# sch_smarthome.net
KiCad netlist of a schematic drawn in Altium Designer
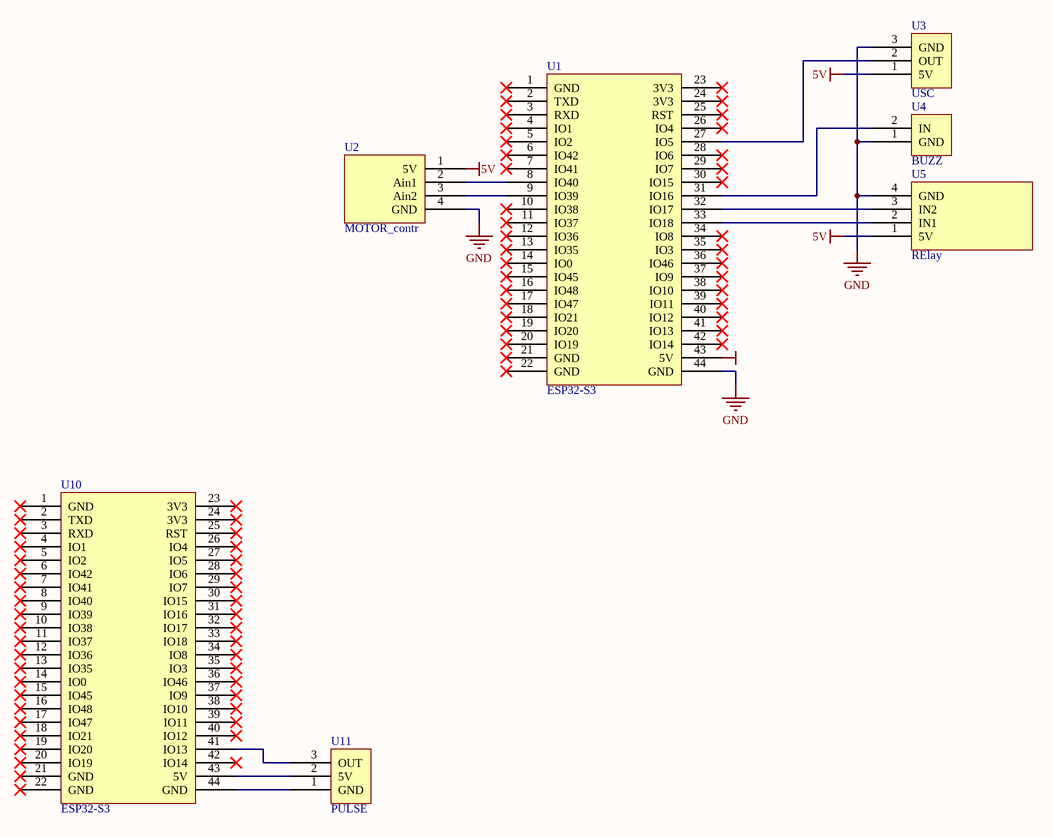
[diagram p0: sch_smarthome.SchDoc]

(export (version "E")
  (design (tool "Eeschema 10.0.6"))
  (components
    (comp (ref "U1") (value "ESP32-S3") (libsource (lib "First_PCB_dip") (part "ESP32-S3")))
    (comp (ref "U2") (value "MOTOR_contr") (libsource (lib "lib_htx") (part "MOTOR_contr")))
    (comp (ref "U3") (value "USC") (libsource (lib "lib_htx") (part "USC")))
    (comp (ref "U4") (value "BUZZ") (libsource (lib "lib_htx") (part "BUZZ")))
    (comp (ref "U5") (value "RElay") (libsource (lib "lib_htx") (part "RElay")))
    (comp (ref "U10") (value "ESP32-S3") (libsource (lib "First_PCB_dip") (part "ESP32-S3")))
    (comp (ref "U11") (value "PULSE") (libsource (lib "lib_htx") (part "PULSE")))
  )
  (nets
    (net (code "1") (name "5V") (class "Default")
      (node (ref "U2") (pin "1") (pinfunction "5V_1") (pintype "passive"))
      (node (ref "U3") (pin "1") (pinfunction "5V_1") (pintype "passive"))
      (node (ref "U5") (pin "1") (pinfunction "5V_1") (pintype "passive"))
    )
    (net (code "2") (name "<NO NET>") (class "Default")
      (node (ref "U1") (pin "43") (pinfunction "5V_43") (pintype "passive"))
    )
    (net (code "3") (name "GND") (class "Default")
      (node (ref "U1") (pin "44") (pinfunction "GND_44") (pintype "passive"))
      (node (ref "U2") (pin "4") (pinfunction "GND_4") (pintype "passive"))
      (node (ref "U3") (pin "3") (pinfunction "GND_3") (pintype "passive"))
      (node (ref "U4") (pin "1") (pinfunction "GND_1") (pintype "passive"))
      (node (ref "U5") (pin "4") (pinfunction "GND_4") (pintype "passive"))
    )
    (net (code "4") (name "Net-(U1-IO5)") (class "Default")
      (node (ref "U1") (pin "27") (pinfunction "IO5_27") (pintype "passive"))
      (node (ref "U3") (pin "2") (pinfunction "OUT_2") (pintype "passive"))
    )
    (net (code "5") (name "Net-(U1-IO16)") (class "Default")
      (node (ref "U1") (pin "31") (pinfunction "IO16_31") (pintype "passive"))
      (node (ref "U4") (pin "2") (pinfunction "IN_2") (pintype "passive"))
    )
    (net (code "6") (name "Net-(U1-IO17)") (class "Default")
      (node (ref "U1") (pin "32") (pinfunction "IO17_32") (pintype "passive"))
      (node (ref "U5") (pin "3") (pinfunction "IN2_3") (pintype "passive"))
    )
    (net (code "7") (name "Net-(U1-IO18)") (class "Default")
      (node (ref "U1") (pin "33") (pinfunction "IO18_33") (pintype "passive"))
      (node (ref "U5") (pin "2") (pinfunction "IN1_2") (pintype "passive"))
    )
    (net (code "8") (name "Net-(U1-IO39)") (class "Default")
      (node (ref "U1") (pin "9") (pinfunction "IO39_9") (pintype "passive"))
      (node (ref "U2") (pin "3") (pinfunction "Ain2_3") (pintype "passive"))
    )
    (net (code "9") (name "Net-(U1-IO40)") (class "Default")
      (node (ref "U1") (pin "8") (pinfunction "IO40_8") (pintype "passive"))
      (node (ref "U2") (pin "2") (pinfunction "Ain1_2") (pintype "passive"))
    )
    (net (code "10") (name "Net-(U10-5V)") (class "Default")
      (node (ref "U10") (pin "43") (pinfunction "5V_43") (pintype "passive"))
      (node (ref "U11") (pin "2") (pinfunction "5V_2") (pintype "passive"))
    )
    (net (code "11") (name "Net-(U10-IO13)") (class "Default")
      (node (ref "U10") (pin "41") (pinfunction "IO13_41") (pintype "passive"))
      (node (ref "U11") (pin "3") (pinfunction "OUT_3") (pintype "passive"))
    )
    (net (code "12") (name "Net-(U11-GND)") (class "Default")
      (node (ref "U10") (pin "44") (pinfunction "GND_44") (pintype "passive"))
      (node (ref "U11") (pin "1") (pinfunction "GND_1") (pintype "passive"))
    )
    (net (code "13") (name "unconnected-(U1-3V3-Pad23)") (class "Default")
      (node (ref "U1") (pin "23") (pinfunction "3V3_23") (pintype "passive+no_connect"))
    )
    (net (code "14") (name "unconnected-(U1-3V3-Pad24)") (class "Default")
      (node (ref "U1") (pin "24") (pinfunction "3V3_24") (pintype "passive+no_connect"))
    )
    (net (code "15") (name "unconnected-(U1-GND-Pad1)") (class "Default")
      (node (ref "U1") (pin "1") (pinfunction "GND_1") (pintype "passive+no_connect"))
    )
    (net (code "16") (name "unconnected-(U1-GND-Pad21)") (class "Default")
      (node (ref "U1") (pin "21") (pinfunction "GND_21") (pintype "passive+no_connect"))
    )
    (net (code "17") (name "unconnected-(U1-GND-Pad22)") (class "Default")
      (node (ref "U1") (pin "22") (pinfunction "GND_22") (pintype "passive+no_connect"))
    )
    (net (code "18") (name "unconnected-(U1-IO0-Pad14)") (class "Default")
      (node (ref "U1") (pin "14") (pinfunction "IO0_14") (pintype "passive+no_connect"))
    )
    (net (code "19") (name "unconnected-(U1-IO1-Pad4)") (class "Default")
      (node (ref "U1") (pin "4") (pinfunction "IO1_4") (pintype "passive+no_connect"))
    )
    (net (code "20") (name "unconnected-(U1-IO2-Pad5)") (class "Default")
      (node (ref "U1") (pin "5") (pinfunction "IO2_5") (pintype "passive+no_connect"))
    )
    (net (code "21") (name "unconnected-(U1-IO3-Pad35)") (class "Default")
      (node (ref "U1") (pin "35") (pinfunction "IO3_35") (pintype "passive+no_connect"))
    )
    (net (code "22") (name "unconnected-(U1-IO4-Pad26)") (class "Default")
      (node (ref "U1") (pin "26") (pinfunction "IO4_26") (pintype "passive+no_connect"))
    )
    (net (code "23") (name "unconnected-(U1-IO6-Pad28)") (class "Default")
      (node (ref "U1") (pin "28") (pinfunction "IO6_28") (pintype "passive+no_connect"))
    )
    (net (code "24") (name "unconnected-(U1-IO7-Pad29)") (class "Default")
      (node (ref "U1") (pin "29") (pinfunction "IO7_29") (pintype "passive+no_connect"))
    )
    (net (code "25") (name "unconnected-(U1-IO8-Pad34)") (class "Default")
      (node (ref "U1") (pin "34") (pinfunction "IO8_34") (pintype "passive+no_connect"))
    )
    (net (code "26") (name "unconnected-(U1-IO9-Pad37)") (class "Default")
      (node (ref "U1") (pin "37") (pinfunction "IO9_37") (pintype "passive+no_connect"))
    )
    (net (code "27") (name "unconnected-(U1-IO10-Pad38)") (class "Default")
      (node (ref "U1") (pin "38") (pinfunction "IO10_38") (pintype "passive+no_connect"))
    )
    (net (code "28") (name "unconnected-(U1-IO11-Pad39)") (class "Default")
      (node (ref "U1") (pin "39") (pinfunction "IO11_39") (pintype "passive+no_connect"))
    )
    (net (code "29") (name "unconnected-(U1-IO12-Pad40)") (class "Default")
      (node (ref "U1") (pin "40") (pinfunction "IO12_40") (pintype "passive+no_connect"))
    )
    (net (code "30") (name "unconnected-(U1-IO13-Pad41)") (class "Default")
      (node (ref "U1") (pin "41") (pinfunction "IO13_41") (pintype "passive+no_connect"))
    )
    (net (code "31") (name "unconnected-(U1-IO14-Pad42)") (class "Default")
      (node (ref "U1") (pin "42") (pinfunction "IO14_42") (pintype "passive+no_connect"))
    )
    (net (code "32") (name "unconnected-(U1-IO15-Pad30)") (class "Default")
      (node (ref "U1") (pin "30") (pinfunction "IO15_30") (pintype "passive+no_connect"))
    )
    (net (code "33") (name "unconnected-(U1-IO19-Pad20)") (class "Default")
      (node (ref "U1") (pin "20") (pinfunction "IO19_20") (pintype "passive+no_connect"))
    )
    (net (code "34") (name "unconnected-(U1-IO20-Pad19)") (class "Default")
      (node (ref "U1") (pin "19") (pinfunction "IO20_19") (pintype "passive+no_connect"))
    )
    (net (code "35") (name "unconnected-(U1-IO21-Pad18)") (class "Default")
      (node (ref "U1") (pin "18") (pinfunction "IO21_18") (pintype "passive+no_connect"))
    )
    (net (code "36") (name "unconnected-(U1-IO35-Pad13)") (class "Default")
      (node (ref "U1") (pin "13") (pinfunction "IO35_13") (pintype "passive+no_connect"))
    )
    (net (code "37") (name "unconnected-(U1-IO36-Pad12)") (class "Default")
      (node (ref "U1") (pin "12") (pinfunction "IO36_12") (pintype "passive+no_connect"))
    )
    (net (code "38") (name "unconnected-(U1-IO37-Pad11)") (class "Default")
      (node (ref "U1") (pin "11") (pinfunction "IO37_11") (pintype "passive+no_connect"))
    )
    (net (code "39") (name "unconnected-(U1-IO38-Pad10)") (class "Default")
      (node (ref "U1") (pin "10") (pinfunction "IO38_10") (pintype "passive+no_connect"))
    )
    (net (code "40") (name "unconnected-(U1-IO41-Pad7)") (class "Default")
      (node (ref "U1") (pin "7") (pinfunction "IO41_7") (pintype "passive+no_connect"))
    )
    (net (code "41") (name "unconnected-(U1-IO42-Pad6)") (class "Default")
      (node (ref "U1") (pin "6") (pinfunction "IO42_6") (pintype "passive+no_connect"))
    )
    (net (code "42") (name "unconnected-(U1-IO45-Pad15)") (class "Default")
      (node (ref "U1") (pin "15") (pinfunction "IO45_15") (pintype "passive+no_connect"))
    )
    (net (code "43") (name "unconnected-(U1-IO46-Pad36)") (class "Default")
      (node (ref "U1") (pin "36") (pinfunction "IO46_36") (pintype "passive+no_connect"))
    )
    (net (code "44") (name "unconnected-(U1-IO47-Pad17)") (class "Default")
      (node (ref "U1") (pin "17") (pinfunction "IO47_17") (pintype "passive+no_connect"))
    )
    (net (code "45") (name "unconnected-(U1-IO48-Pad16)") (class "Default")
      (node (ref "U1") (pin "16") (pinfunction "IO48_16") (pintype "passive+no_connect"))
    )
    (net (code "46") (name "unconnected-(U1-RST-Pad25)") (class "Default")
      (node (ref "U1") (pin "25") (pinfunction "RST_25") (pintype "passive+no_connect"))
    )
    (net (code "47") (name "unconnected-(U1-RXD-Pad3)") (class "Default")
      (node (ref "U1") (pin "3") (pinfunction "RXD_3") (pintype "passive+no_connect"))
    )
    (net (code "48") (name "unconnected-(U1-TXD-Pad2)") (class "Default")
      (node (ref "U1") (pin "2") (pinfunction "TXD_2") (pintype "passive+no_connect"))
    )
    (net (code "49") (name "unconnected-(U10-3V3-Pad23)") (class "Default")
      (node (ref "U10") (pin "23") (pinfunction "3V3_23") (pintype "passive+no_connect"))
    )
    (net (code "50") (name "unconnected-(U10-3V3-Pad24)") (class "Default")
      (node (ref "U10") (pin "24") (pinfunction "3V3_24") (pintype "passive+no_connect"))
    )
    (net (code "51") (name "unconnected-(U10-GND-Pad1)") (class "Default")
      (node (ref "U10") (pin "1") (pinfunction "GND_1") (pintype "passive+no_connect"))
    )
    (net (code "52") (name "unconnected-(U10-GND-Pad21)") (class "Default")
      (node (ref "U10") (pin "21") (pinfunction "GND_21") (pintype "passive+no_connect"))
    )
    (net (code "53") (name "unconnected-(U10-GND-Pad22)") (class "Default")
      (node (ref "U10") (pin "22") (pinfunction "GND_22") (pintype "passive+no_connect"))
    )
    (net (code "54") (name "unconnected-(U10-IO0-Pad14)") (class "Default")
      (node (ref "U10") (pin "14") (pinfunction "IO0_14") (pintype "passive+no_connect"))
    )
    (net (code "55") (name "unconnected-(U10-IO1-Pad4)") (class "Default")
      (node (ref "U10") (pin "4") (pinfunction "IO1_4") (pintype "passive+no_connect"))
    )
    (net (code "56") (name "unconnected-(U10-IO2-Pad5)") (class "Default")
      (node (ref "U10") (pin "5") (pinfunction "IO2_5") (pintype "passive+no_connect"))
    )
    (net (code "57") (name "unconnected-(U10-IO3-Pad35)") (class "Default")
      (node (ref "U10") (pin "35") (pinfunction "IO3_35") (pintype "passive+no_connect"))
    )
    (net (code "58") (name "unconnected-(U10-IO4-Pad26)") (class "Default")
      (node (ref "U10") (pin "26") (pinfunction "IO4_26") (pintype "passive+no_connect"))
    )
    (net (code "59") (name "unconnected-(U10-IO5-Pad27)") (class "Default")
      (node (ref "U10") (pin "27") (pinfunction "IO5_27") (pintype "passive+no_connect"))
    )
    (net (code "60") (name "unconnected-(U10-IO6-Pad28)") (class "Default")
      (node (ref "U10") (pin "28") (pinfunction "IO6_28") (pintype "passive+no_connect"))
    )
    (net (code "61") (name "unconnected-(U10-IO7-Pad29)") (class "Default")
      (node (ref "U10") (pin "29") (pinfunction "IO7_29") (pintype "passive+no_connect"))
    )
    (net (code "62") (name "unconnected-(U10-IO8-Pad34)") (class "Default")
      (node (ref "U10") (pin "34") (pinfunction "IO8_34") (pintype "passive+no_connect"))
    )
    (net (code "63") (name "unconnected-(U10-IO9-Pad37)") (class "Default")
      (node (ref "U10") (pin "37") (pinfunction "IO9_37") (pintype "passive+no_connect"))
    )
    (net (code "64") (name "unconnected-(U10-IO10-Pad38)") (class "Default")
      (node (ref "U10") (pin "38") (pinfunction "IO10_38") (pintype "passive+no_connect"))
    )
    (net (code "65") (name "unconnected-(U10-IO11-Pad39)") (class "Default")
      (node (ref "U10") (pin "39") (pinfunction "IO11_39") (pintype "passive+no_connect"))
    )
    (net (code "66") (name "unconnected-(U10-IO12-Pad40)") (class "Default")
      (node (ref "U10") (pin "40") (pinfunction "IO12_40") (pintype "passive+no_connect"))
    )
    (net (code "67") (name "unconnected-(U10-IO14-Pad42)") (class "Default")
      (node (ref "U10") (pin "42") (pinfunction "IO14_42") (pintype "passive+no_connect"))
    )
    (net (code "68") (name "unconnected-(U10-IO15-Pad30)") (class "Default")
      (node (ref "U10") (pin "30") (pinfunction "IO15_30") (pintype "passive+no_connect"))
    )
    (net (code "69") (name "unconnected-(U10-IO16-Pad31)") (class "Default")
      (node (ref "U10") (pin "31") (pinfunction "IO16_31") (pintype "passive+no_connect"))
    )
    (net (code "70") (name "unconnected-(U10-IO17-Pad32)") (class "Default")
      (node (ref "U10") (pin "32") (pinfunction "IO17_32") (pintype "passive+no_connect"))
    )
    (net (code "71") (name "unconnected-(U10-IO18-Pad33)") (class "Default")
      (node (ref "U10") (pin "33") (pinfunction "IO18_33") (pintype "passive+no_connect"))
    )
    (net (code "72") (name "unconnected-(U10-IO19-Pad20)") (class "Default")
      (node (ref "U10") (pin "20") (pinfunction "IO19_20") (pintype "passive+no_connect"))
    )
    (net (code "73") (name "unconnected-(U10-IO20-Pad19)") (class "Default")
      (node (ref "U10") (pin "19") (pinfunction "IO20_19") (pintype "passive+no_connect"))
    )
    (net (code "74") (name "unconnected-(U10-IO21-Pad18)") (class "Default")
      (node (ref "U10") (pin "18") (pinfunction "IO21_18") (pintype "passive+no_connect"))
    )
    (net (code "75") (name "unconnected-(U10-IO35-Pad13)") (class "Default")
      (node (ref "U10") (pin "13") (pinfunction "IO35_13") (pintype "passive+no_connect"))
    )
    (net (code "76") (name "unconnected-(U10-IO36-Pad12)") (class "Default")
      (node (ref "U10") (pin "12") (pinfunction "IO36_12") (pintype "passive+no_connect"))
    )
    (net (code "77") (name "unconnected-(U10-IO37-Pad11)") (class "Default")
      (node (ref "U10") (pin "11") (pinfunction "IO37_11") (pintype "passive+no_connect"))
    )
    (net (code "78") (name "unconnected-(U10-IO38-Pad10)") (class "Default")
      (node (ref "U10") (pin "10") (pinfunction "IO38_10") (pintype "passive+no_connect"))
    )
    (net (code "79") (name "unconnected-(U10-IO39-Pad9)") (class "Default")
      (node (ref "U10") (pin "9") (pinfunction "IO39_9") (pintype "passive+no_connect"))
    )
    (net (code "80") (name "unconnected-(U10-IO40-Pad8)") (class "Default")
      (node (ref "U10") (pin "8") (pinfunction "IO40_8") (pintype "passive+no_connect"))
    )
    (net (code "81") (name "unconnected-(U10-IO41-Pad7)") (class "Default")
      (node (ref "U10") (pin "7") (pinfunction "IO41_7") (pintype "passive+no_connect"))
    )
    (net (code "82") (name "unconnected-(U10-IO42-Pad6)") (class "Default")
      (node (ref "U10") (pin "6") (pinfunction "IO42_6") (pintype "passive+no_connect"))
    )
    (net (code "83") (name "unconnected-(U10-IO45-Pad15)") (class "Default")
      (node (ref "U10") (pin "15") (pinfunction "IO45_15") (pintype "passive+no_connect"))
    )
    (net (code "84") (name "unconnected-(U10-IO46-Pad36)") (class "Default")
      (node (ref "U10") (pin "36") (pinfunction "IO46_36") (pintype "passive+no_connect"))
    )
    (net (code "85") (name "unconnected-(U10-IO47-Pad17)") (class "Default")
      (node (ref "U10") (pin "17") (pinfunction "IO47_17") (pintype "passive+no_connect"))
    )
    (net (code "86") (name "unconnected-(U10-IO48-Pad16)") (class "Default")
      (node (ref "U10") (pin "16") (pinfunction "IO48_16") (pintype "passive+no_connect"))
    )
    (net (code "87") (name "unconnected-(U10-RST-Pad25)") (class "Default")
      (node (ref "U10") (pin "25") (pinfunction "RST_25") (pintype "passive+no_connect"))
    )
    (net (code "88") (name "unconnected-(U10-RXD-Pad3)") (class "Default")
      (node (ref "U10") (pin "3") (pinfunction "RXD_3") (pintype "passive+no_connect"))
    )
    (net (code "89") (name "unconnected-(U10-TXD-Pad2)") (class "Default")
      (node (ref "U10") (pin "2") (pinfunction "TXD_2") (pintype "passive+no_connect"))
    )
  )
)
